# fan-controller.net
KiCad netlist of a schematic drawn in EAGLE
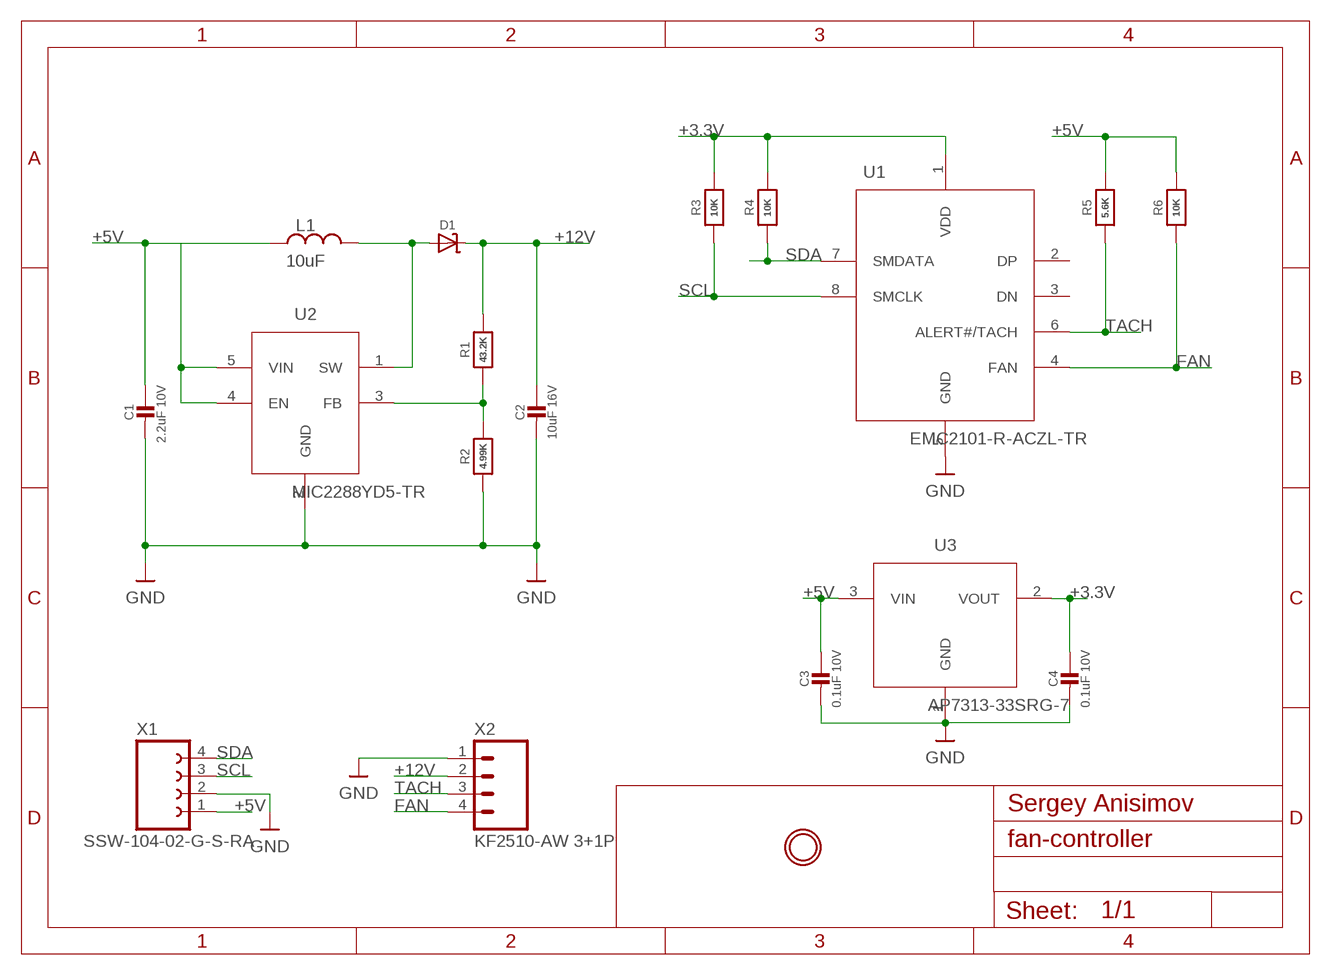
[diagram p0: schematic, sheet 1]

(export (version "E")
  (design (tool "Eeschema 10.0.6"))
  (components
    (comp (ref "C1")
      (value "2.2uF 10V")
      (footprint "eagle-import:CAPC1608X50N")
      (libsource (lib "eagle-import") (part "CAPACITORCAP_0603"))
    )
    (comp (ref "C2")
      (value "10uF 16V")
      (footprint "eagle-import:CAPC2012X139N")
      (libsource (lib "eagle-import") (part "CAPACITORCAP_0805"))
    )
    (comp (ref "C3")
      (value "0.1uF 10V")
      (footprint "eagle-import:CAPC1205X55N")
      (libsource (lib "eagle-import") (part "CAPACITORCAP_0402_L"))
    )
    (comp (ref "C4")
      (value "0.1uF 10V")
      (footprint "eagle-import:CAPC1205X55N")
      (libsource (lib "eagle-import") (part "CAPACITORCAP_0402_L"))
    )
    (comp (ref "D1")
      (value "DIODE-SCHOTTKY")
      (footprint "eagle-import:CASE457−04")
      (libsource (lib "eagle-import") (part "DIODE-SCHOTTKY"))
    )
    (comp (ref "L1")
      (value "10uF")
      (footprint "eagle-import:INDC3225X270")
      (libsource (lib "eagle-import") (part "INDUCTOR"))
    )
    (comp (ref "R1")
      (value "43.2K")
      (footprint "eagle-import:RESC1608X55N")
      (libsource (lib "eagle-import") (part "RESISTOR0603"))
    )
    (comp (ref "R2")
      (value "4.99K")
      (footprint "eagle-import:RESC1608X55N")
      (libsource (lib "eagle-import") (part "RESISTOR0603"))
    )
    (comp (ref "R3")
      (value "10K")
      (footprint "eagle-import:RESC1005X40N")
      (libsource (lib "eagle-import") (part "RESISTOR0402"))
    )
    (comp (ref "R4")
      (value "10K")
      (footprint "eagle-import:RESC1005X40N")
      (libsource (lib "eagle-import") (part "RESISTOR0402"))
    )
    (comp (ref "R5")
      (value "5.6K")
      (footprint "eagle-import:RESC1005X40N")
      (libsource (lib "eagle-import") (part "RESISTOR0402"))
    )
    (comp (ref "R6")
      (value "10K")
      (footprint "eagle-import:RESC1005X40N")
      (libsource (lib "eagle-import") (part "RESISTOR0402"))
    )
    (comp (ref "U$7")
      (value "MOUNTING-HOLE2.7_THICK")
      (footprint "eagle-import:MOUNTINGHOLE_2.7_PLATED_THICK")
      (libsource (lib "eagle-import") (part "MOUNTING-HOLE2.7_THICK"))
    )
    (comp (ref "U1")
      (value "EMC2101-R-ACZL-TR")
      (footprint "eagle-import:SOP65P490X110-8N")
      (libsource (lib "eagle-import") (part "EMC21018-PIN-TSSOP"))
    )
    (comp (ref "U2")
      (value "MIC2288YD5-TR")
      (footprint "eagle-import:SOT95P279X100-5")
      (libsource (lib "eagle-import") (part "MIC2288YD5"))
    )
    (comp (ref "U3")
      (value "AP7313-33SRG-7")
      (footprint "eagle-import:SOT95P240X120-3")
      (libsource (lib "eagle-import") (part "LDO-3PINSOT23-GND-OUT-IN"))
    )
    (comp (ref "X1")
      (value "SSW-104-02-G-S-RA")
      (footprint "eagle-import:HDRRAR4W64P254_1X4_1067X851X241B")
      (libsource (lib "eagle-import") (part "CON-FE-04-01"))
    )
    (comp (ref "X2")
      (value "KF2510-AW 3+1P")
      (footprint "eagle-import:HDRRA4W64P254_1X4_1016X300X580B")
      (libsource (lib "eagle-import") (part "CON-MA-04-01"))
    )
  )
  (nets
    (net (code "1") (name "/+3.3V") (class "Default")
      (node (ref "C4") (pin "1") (pinfunction "1_1") (pintype "passive"))
      (node (ref "R3") (pin "2") (pinfunction "2_2") (pintype "passive"))
      (node (ref "R4") (pin "2") (pinfunction "2_2") (pintype "passive"))
      (node (ref "U1") (pin "1") (pinfunction "VDD_1") (pintype "bidirectional"))
      (node (ref "U3") (pin "2") (pinfunction "VOUT_2") (pintype "bidirectional"))
    )
    (net (code "2") (name "/+5V") (class "Default")
      (node (ref "C1") (pin "1") (pinfunction "1_1") (pintype "passive"))
      (node (ref "C3") (pin "1") (pinfunction "1_1") (pintype "passive"))
      (node (ref "L1") (pin "1") (pinfunction "1_1") (pintype "passive"))
      (node (ref "R5") (pin "2") (pinfunction "2_2") (pintype "passive"))
      (node (ref "R6") (pin "2") (pinfunction "2_2") (pintype "passive"))
      (node (ref "U2") (pin "4") (pinfunction "EN_4") (pintype "bidirectional"))
      (node (ref "U2") (pin "5") (pinfunction "VIN_5") (pintype "bidirectional"))
      (node (ref "U3") (pin "3") (pinfunction "VIN_3") (pintype "bidirectional"))
      (node (ref "X1") (pin "1") (pinfunction "1_1") (pintype "passive"))
    )
    (net (code "3") (name "/+12V") (class "Default")
      (node (ref "C2") (pin "1") (pinfunction "1_1") (pintype "passive"))
      (node (ref "D1") (pin "C") (pinfunction "C_C") (pintype "passive"))
      (node (ref "R1") (pin "1") (pinfunction "1_1") (pintype "passive"))
      (node (ref "X2") (pin "2") (pinfunction "2_2") (pintype "passive"))
    )
    (net (code "4") (name "/FAN") (class "Default")
      (node (ref "R6") (pin "1") (pinfunction "1_1") (pintype "passive"))
      (node (ref "U1") (pin "4") (pinfunction "FAN_4") (pintype "bidirectional"))
      (node (ref "X2") (pin "4") (pinfunction "4_4") (pintype "passive"))
    )
    (net (code "5") (name "/SCL") (class "Default")
      (node (ref "R3") (pin "1") (pinfunction "1_1") (pintype "passive"))
      (node (ref "U1") (pin "8") (pinfunction "SMCLK_8") (pintype "bidirectional"))
      (node (ref "X1") (pin "3") (pinfunction "3_3") (pintype "passive"))
    )
    (net (code "6") (name "/SDA") (class "Default")
      (node (ref "R4") (pin "1") (pinfunction "1_1") (pintype "passive"))
      (node (ref "U1") (pin "7") (pinfunction "SMDATA_7") (pintype "bidirectional"))
      (node (ref "X1") (pin "4") (pinfunction "4_4") (pintype "passive"))
    )
    (net (code "7") (name "/TACH") (class "Default")
      (node (ref "R5") (pin "1") (pinfunction "1_1") (pintype "passive"))
      (node (ref "U1") (pin "6") (pinfunction "ALERT#/TACH_6") (pintype "bidirectional"))
      (node (ref "X2") (pin "3") (pinfunction "3_3") (pintype "passive"))
    )
    (net (code "8") (name "GND") (class "Default")
      (node (ref "C1") (pin "2") (pinfunction "2_2") (pintype "passive"))
      (node (ref "C2") (pin "2") (pinfunction "2_2") (pintype "passive"))
      (node (ref "C3") (pin "2") (pinfunction "2_2") (pintype "passive"))
      (node (ref "C4") (pin "2") (pinfunction "2_2") (pintype "passive"))
      (node (ref "R2") (pin "1") (pinfunction "1_1") (pintype "passive"))
      (node (ref "U1") (pin "5") (pinfunction "GND_5") (pintype "bidirectional"))
      (node (ref "U2") (pin "2") (pinfunction "GND_2") (pintype "bidirectional"))
      (node (ref "U3") (pin "1") (pinfunction "GND_1") (pintype "bidirectional"))
      (node (ref "X1") (pin "2") (pinfunction "2_2") (pintype "passive"))
      (node (ref "X2") (pin "1") (pinfunction "1_1") (pintype "passive"))
    )
    (net (code "9") (name "Net-(U2-FB)") (class "Default")
      (node (ref "R1") (pin "2") (pinfunction "2_2") (pintype "passive"))
      (node (ref "R2") (pin "2") (pinfunction "2_2") (pintype "passive"))
      (node (ref "U2") (pin "3") (pinfunction "FB_3") (pintype "bidirectional"))
    )
    (net (code "10") (name "Net-(U2-SW)") (class "Default")
      (node (ref "D1") (pin "A") (pinfunction "A_A") (pintype "passive"))
      (node (ref "L1") (pin "2") (pinfunction "2_2") (pintype "passive"))
      (node (ref "U2") (pin "1") (pinfunction "SW_1") (pintype "bidirectional"))
    )
    (net (code "11") (name "unconnected-(U1-DN-Pad3)") (class "Default")
      (node (ref "U1") (pin "3") (pinfunction "DN_3") (pintype "bidirectional"))
    )
    (net (code "12") (name "unconnected-(U1-DP-Pad2)") (class "Default")
      (node (ref "U1") (pin "2") (pinfunction "DP_2") (pintype "bidirectional"))
    )
  )
)
